# pavement_painter.net
KiCad netlist of a schematic drawn in EAGLE
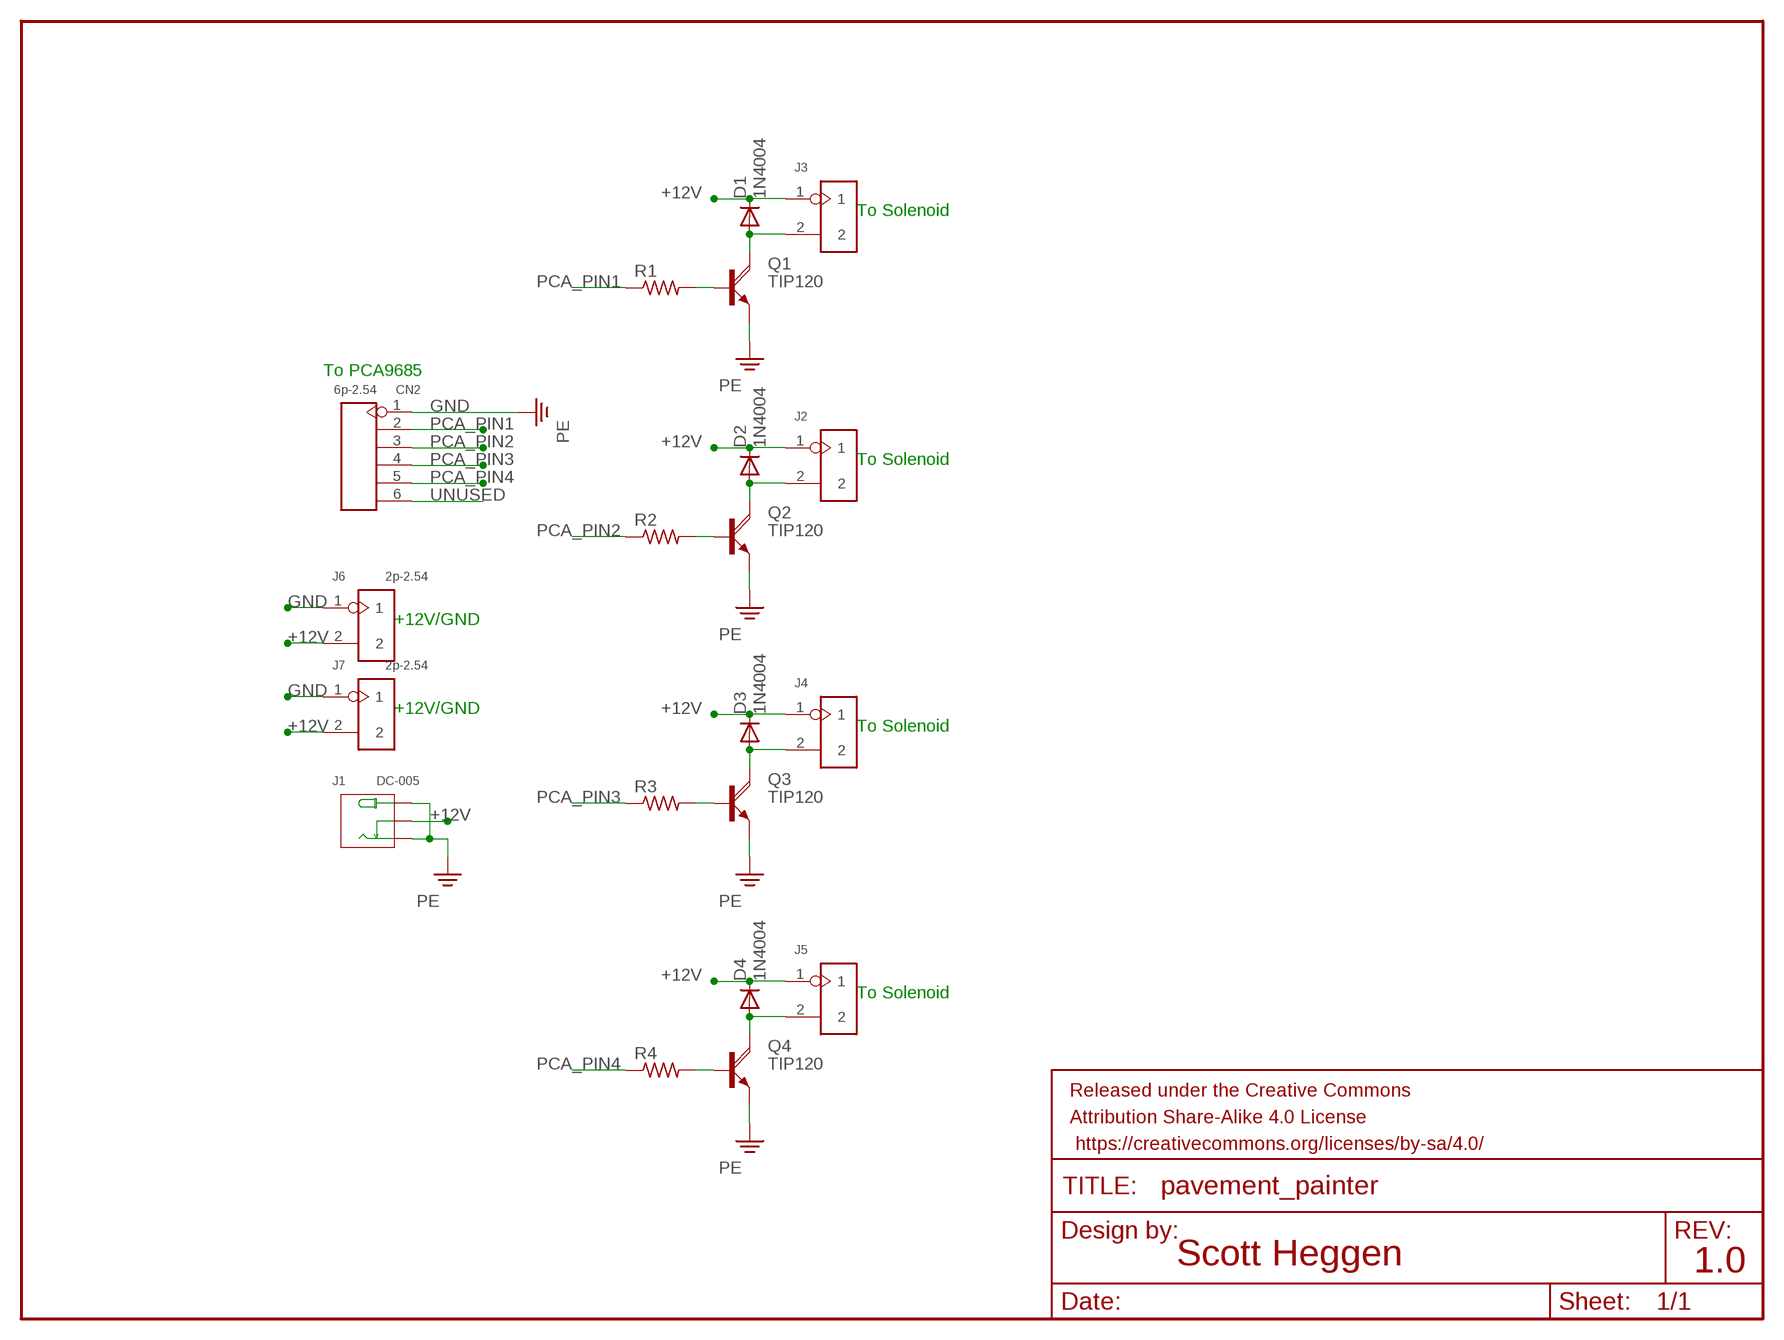
[diagram p0: schematic, sheet 1]

(export (version "E")
  (design (tool "Eeschema 10.0.6"))
  (components
    (comp (ref "CN2")
      (value "6p-2.54")
      (footprint "eagle-import:H6-2.54")
      (fields (field (name "MPN") "F185-1106A1BSYC1"))
      (libsource (lib "eagle-import") (part "DIP-BLACK-FEMALE-HEADER-VERT(6P-2.54)"))
    )
    (comp (ref "D1")
      (value "1N4004")
      (footprint "eagle-import:DO41-10")
      (libsource (lib "eagle-import") (part "1N4004"))
    )
    (comp (ref "D2")
      (value "1N4004")
      (footprint "eagle-import:DO41-10")
      (libsource (lib "eagle-import") (part "1N4004"))
    )
    (comp (ref "D3")
      (value "1N4004")
      (footprint "eagle-import:DO41-10")
      (libsource (lib "eagle-import") (part "1N4004"))
    )
    (comp (ref "D4")
      (value "1N4004")
      (footprint "eagle-import:DO41-10")
      (libsource (lib "eagle-import") (part "1N4004"))
    )
    (comp (ref "FRAME1")
      (value "FRAME-LETTER")
      (footprint "eagle-import:CREATIVE_COMMONS")
      (libsource (lib "eagle-import") (part "FRAME-LETTER"))
    )
    (comp (ref "J1")
      (value "DC-005")
      (footprint "eagle-import:DCJ3P-14.2X11.0X9.0MM")
      (libsource (lib "eagle-import") (part "CONN-POWER-JACK-2.1MM(DC-005)"))
    )
    (comp (ref "J2")
      (value "DIP-BLACK-JUMPER")
      (footprint "eagle-import:H2-2.54")
      (libsource (lib "eagle-import") (part "DIP-BLACK-JUMPER"))
    )
    (comp (ref "J3")
      (value "DIP-BLACK-JUMPER")
      (footprint "eagle-import:H2-2.54")
      (libsource (lib "eagle-import") (part "DIP-BLACK-JUMPER"))
    )
    (comp (ref "J4")
      (value "DIP-BLACK-JUMPER")
      (footprint "eagle-import:H2-2.54")
      (libsource (lib "eagle-import") (part "DIP-BLACK-JUMPER"))
    )
    (comp (ref "J5")
      (value "DIP-BLACK-JUMPER")
      (footprint "eagle-import:H2-2.54")
      (libsource (lib "eagle-import") (part "DIP-BLACK-JUMPER"))
    )
    (comp (ref "J6")
      (value "2p-2.54")
      (footprint "eagle-import:H2-2.54")
      (fields (field (name "MPN") "P125-1102A0BS116A1"))
      (libsource (lib "eagle-import") (part "DIP-BLACK-MALE-HEADER-VERT(2P-2.54)"))
    )
    (comp (ref "J7")
      (value "2p-2.54")
      (footprint "eagle-import:H2-2.54")
      (fields (field (name "MPN") "P125-1102A0BS116A1"))
      (libsource (lib "eagle-import") (part "DIP-BLACK-MALE-HEADER-VERT(2P-2.54)"))
    )
    (comp (ref "Q1")
      (value "TIP120")
      (footprint "eagle-import:TO220AH")
      (libsource (lib "eagle-import") (part "TIP120"))
    )
    (comp (ref "Q2")
      (value "TIP120")
      (footprint "eagle-import:TO220AH")
      (libsource (lib "eagle-import") (part "TIP120"))
    )
    (comp (ref "Q3")
      (value "TIP120")
      (footprint "eagle-import:TO220AH")
      (libsource (lib "eagle-import") (part "TIP120"))
    )
    (comp (ref "Q4")
      (value "TIP120")
      (footprint "eagle-import:TO220AH")
      (libsource (lib "eagle-import") (part "TIP120"))
    )
    (comp (ref "R1")
      (value "R-US_0207/12")
      (footprint "eagle-import:0207_12")
      (libsource (lib "eagle-import") (part "R-US_0207/12"))
    )
    (comp (ref "R2")
      (value "R-US_0207/12")
      (footprint "eagle-import:0207_12")
      (libsource (lib "eagle-import") (part "R-US_0207/12"))
    )
    (comp (ref "R3")
      (value "R-US_0207/12")
      (footprint "eagle-import:0207_12")
      (libsource (lib "eagle-import") (part "R-US_0207/12"))
    )
    (comp (ref "R4")
      (value "R-US_0207/12")
      (footprint "eagle-import:0207_12")
      (libsource (lib "eagle-import") (part "R-US_0207/12"))
    )
  )
  (nets
    (net (code "1") (name "/+12V") (class "Default")
      (node (ref "D1") (pin "C") (pinfunction "C_C") (pintype "passive"))
      (node (ref "D2") (pin "C") (pinfunction "C_C") (pintype "passive"))
      (node (ref "D3") (pin "C") (pinfunction "C_C") (pintype "passive"))
      (node (ref "D4") (pin "C") (pinfunction "C_C") (pintype "passive"))
      (node (ref "J1") (pin "-2") (pinfunction "CDN_-2") (pintype "bidirectional"))
      (node (ref "J2") (pin "1") (pinfunction "1_1") (pintype "bidirectional"))
      (node (ref "J3") (pin "1") (pinfunction "1_1") (pintype "bidirectional"))
      (node (ref "J4") (pin "1") (pinfunction "1_1") (pintype "bidirectional"))
      (node (ref "J5") (pin "1") (pinfunction "1_1") (pintype "bidirectional"))
      (node (ref "J6") (pin "2") (pinfunction "2_2") (pintype "bidirectional"))
      (node (ref "J7") (pin "2") (pinfunction "2_2") (pintype "bidirectional"))
    )
    (net (code "2") (name "/PCA_PIN1") (class "Default")
      (node (ref "CN2") (pin "2") (pinfunction "2_2") (pintype "bidirectional"))
      (node (ref "R1") (pin "1") (pinfunction "1_1") (pintype "passive"))
    )
    (net (code "3") (name "/PCA_PIN2") (class "Default")
      (node (ref "CN2") (pin "3") (pinfunction "3_3") (pintype "bidirectional"))
      (node (ref "R2") (pin "1") (pinfunction "1_1") (pintype "passive"))
    )
    (net (code "4") (name "/PCA_PIN3") (class "Default")
      (node (ref "CN2") (pin "4") (pinfunction "4_4") (pintype "bidirectional"))
      (node (ref "R3") (pin "1") (pinfunction "1_1") (pintype "passive"))
    )
    (net (code "5") (name "/PCA_PIN4") (class "Default")
      (node (ref "CN2") (pin "5") (pinfunction "5_5") (pintype "bidirectional"))
      (node (ref "R4") (pin "1") (pinfunction "1_1") (pintype "passive"))
    )
    (net (code "6") (name "/UNUSED") (class "Default")
      (node (ref "CN2") (pin "6") (pinfunction "6_6") (pintype "bidirectional"))
    )
    (net (code "7") (name "Net-(D1-PadA)") (class "Default")
      (node (ref "D1") (pin "A") (pinfunction "A_A") (pintype "passive"))
      (node (ref "J3") (pin "2") (pinfunction "2_2") (pintype "bidirectional"))
      (node (ref "Q1") (pin "C") (pinfunction "C_C") (pintype "passive"))
    )
    (net (code "8") (name "Net-(D2-PadA)") (class "Default")
      (node (ref "D2") (pin "A") (pinfunction "A_A") (pintype "passive"))
      (node (ref "J2") (pin "2") (pinfunction "2_2") (pintype "bidirectional"))
      (node (ref "Q2") (pin "C") (pinfunction "C_C") (pintype "passive"))
    )
    (net (code "9") (name "Net-(D3-PadA)") (class "Default")
      (node (ref "D3") (pin "A") (pinfunction "A_A") (pintype "passive"))
      (node (ref "J4") (pin "2") (pinfunction "2_2") (pintype "bidirectional"))
      (node (ref "Q3") (pin "C") (pinfunction "C_C") (pintype "passive"))
    )
    (net (code "10") (name "Net-(D4-PadA)") (class "Default")
      (node (ref "D4") (pin "A") (pinfunction "A_A") (pintype "passive"))
      (node (ref "J5") (pin "2") (pinfunction "2_2") (pintype "bidirectional"))
      (node (ref "Q4") (pin "C") (pinfunction "C_C") (pintype "passive"))
    )
    (net (code "11") (name "Net-(Q1-PadB)") (class "Default")
      (node (ref "Q1") (pin "B") (pinfunction "B_B") (pintype "passive"))
      (node (ref "R1") (pin "2") (pinfunction "2_2") (pintype "passive"))
    )
    (net (code "12") (name "Net-(Q2-PadB)") (class "Default")
      (node (ref "Q2") (pin "B") (pinfunction "B_B") (pintype "passive"))
      (node (ref "R2") (pin "2") (pinfunction "2_2") (pintype "passive"))
    )
    (net (code "13") (name "Net-(Q3-PadB)") (class "Default")
      (node (ref "Q3") (pin "B") (pinfunction "B_B") (pintype "passive"))
      (node (ref "R3") (pin "2") (pinfunction "2_2") (pintype "passive"))
    )
    (net (code "14") (name "Net-(Q4-PadB)") (class "Default")
      (node (ref "Q4") (pin "B") (pinfunction "B_B") (pintype "passive"))
      (node (ref "R4") (pin "2") (pinfunction "2_2") (pintype "passive"))
    )
    (net (code "15") (name "PE") (class "Default")
      (node (ref "CN2") (pin "1") (pinfunction "1_1") (pintype "bidirectional"))
      (node (ref "J1") (pin "+") (pinfunction "+_+") (pintype "bidirectional"))
      (node (ref "J1") (pin "-1") (pinfunction "-_-1") (pintype "bidirectional"))
      (node (ref "J6") (pin "1") (pinfunction "1_1") (pintype "bidirectional"))
      (node (ref "J7") (pin "1") (pinfunction "1_1") (pintype "bidirectional"))
      (node (ref "Q1") (pin "E") (pinfunction "E_E") (pintype "passive"))
      (node (ref "Q2") (pin "E") (pinfunction "E_E") (pintype "passive"))
      (node (ref "Q3") (pin "E") (pinfunction "E_E") (pintype "passive"))
      (node (ref "Q4") (pin "E") (pinfunction "E_E") (pintype "passive"))
    )
  )
)
